# ZG-Mxx_MINI-v1_0.net
KiCad netlist of a schematic drawn in Altium Designer
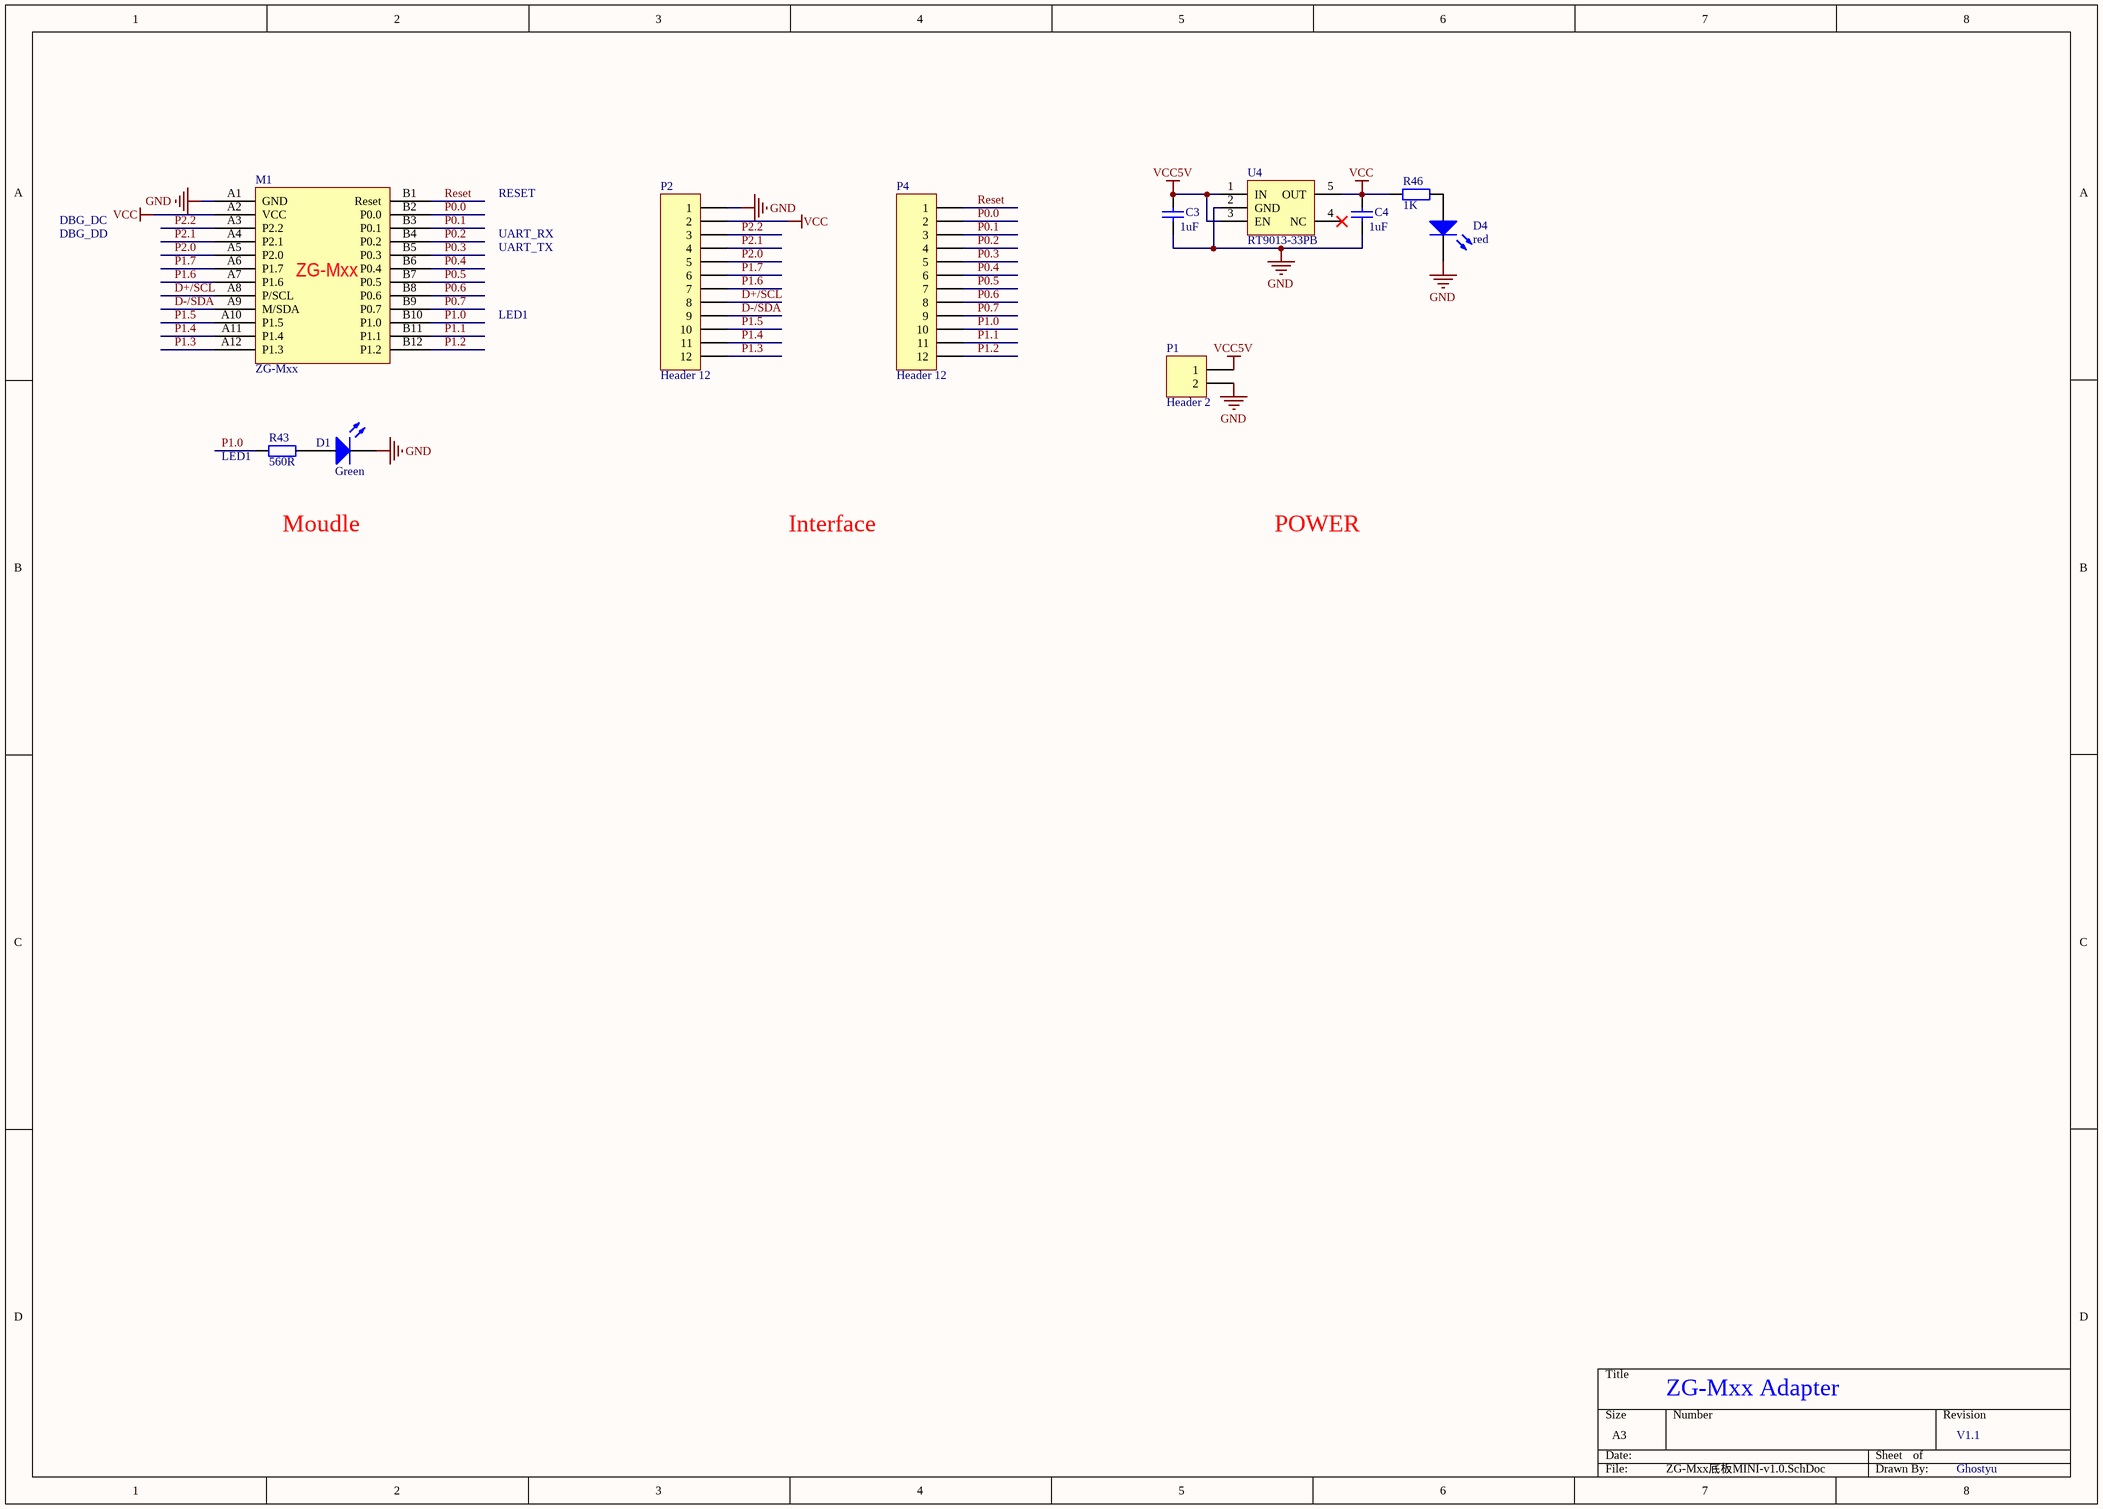
[diagram p0: ZG-Mxx底板MINI-v1.0.SchDoc]

(export (version "E")
  (design (tool "Eeschema 10.0.6"))
  (components
    (comp (ref "C3")
      (value "1uF")
      (footprint "R0603-S")
      (description "Capacitor")
      (fields (field (name "Comment") "Cap") (field (name "PUBLISHER") "Altium Limited"))
      (libsource (lib "Miscellaneous Devices") (part "Cap"))
    )
    (comp (ref "C4")
      (value "1uF")
      (footprint "R0603-S")
      (description "Capacitor")
      (fields (field (name "Comment") "Cap") (field (name "PUBLISHER") "Altium Limited"))
      (libsource (lib "Miscellaneous Devices") (part "Cap"))
    )
    (comp (ref "D1")
      (value "Green")
      (footprint "LED0805")
      (description "Typical RED, GREEN, YELLOW, AMBER GaAs LED")
      (fields (field (name "PUBLISHER") "Altium Limited"))
      (libsource (lib "Miscellaneous Devices") (part "LED2"))
    )
    (comp (ref "D4")
      (value "red")
      (footprint "LED0805")
      (description "Typical RED, GREEN, YELLOW, AMBER GaAs LED")
      (fields (field (name "PUBLISHER") "Altium Limited"))
      (libsource (lib "Miscellaneous Devices") (part "LED2"))
    )
    (comp (ref "M1") (value "ZG-Mxx") (footprint "ZG-M1/1E") (libsource (lib "ZG-Mxx") (part "ZG-Mxx")))
    (comp (ref "P1")
      (value "Header 2")
      (footprint "HDR1X2")
      (description "Header, 2-Pin")
      (fields (field (name "PUBLISHER") "Altium Limited"))
      (libsource (lib "Miscellaneous Connectors") (part "Header 2"))
    )
    (comp (ref "P2")
      (value "Header 12")
      (footprint "HDR2X6")
      (description "Header, 12-Pin")
      (fields (field (name "PUBLISHER") "Altium Limited"))
      (libsource (lib "Miscellaneous Connectors") (part "Header 12"))
    )
    (comp (ref "P4")
      (value "Header 12")
      (footprint "HDR2X6")
      (description "Header, 12-Pin")
      (fields (field (name "PUBLISHER") "Altium Limited"))
      (libsource (lib "Miscellaneous Connectors") (part "Header 12"))
    )
    (comp (ref "R43")
      (value "560R")
      (footprint "R0603-S")
      (description "Resistor")
      (fields (field (name "Comment") "Res2") (field (name "PUBLISHER") "Altium Limited"))
      (libsource (lib "Miscellaneous Devices") (part "Res2"))
    )
    (comp (ref "R46")
      (value "1K")
      (footprint "R0603-S")
      (description "Resistor")
      (fields (field (name "Comment") "Res2") (field (name "PUBLISHER") "Altium Limited"))
      (libsource (lib "Miscellaneous Devices") (part "Res2"))
    )
    (comp (ref "U4")
      (value "RT9013-33PB")
      (footprint "SOT23-5")
      (libsource (lib "Schlib") (part "RT9013-33PB"))
    )
  )
  (nets
    (net (code "1") (name "/D+{slash}SCL") (class "Default")
      (node (ref "M1") (pin "A8") (pinfunction "P/SCL_A8") (pintype "passive"))
      (node (ref "P2") (pin "8") (pinfunction "8_8") (pintype "passive"))
    )
    (net (code "2") (name "/D-{slash}SDA") (class "Default")
      (node (ref "M1") (pin "A9") (pinfunction "M/SDA_A9") (pintype "passive"))
      (node (ref "P2") (pin "9") (pinfunction "9_9") (pintype "passive"))
    )
    (net (code "3") (name "/P0.0") (class "Default")
      (node (ref "M1") (pin "B2") (pinfunction "P0.0_B2") (pintype "passive"))
      (node (ref "P4") (pin "2") (pinfunction "2_2") (pintype "passive"))
    )
    (net (code "4") (name "/P0.1") (class "Default")
      (node (ref "M1") (pin "B3") (pinfunction "P0.1_B3") (pintype "passive"))
      (node (ref "P4") (pin "3") (pinfunction "3_3") (pintype "passive"))
    )
    (net (code "5") (name "/P0.2") (class "Default")
      (node (ref "M1") (pin "B4") (pinfunction "P0.2_B4") (pintype "passive"))
      (node (ref "P4") (pin "4") (pinfunction "4_4") (pintype "passive"))
    )
    (net (code "6") (name "/P0.3") (class "Default")
      (node (ref "M1") (pin "B5") (pinfunction "P0.3_B5") (pintype "passive"))
      (node (ref "P4") (pin "5") (pinfunction "5_5") (pintype "passive"))
    )
    (net (code "7") (name "/P0.4") (class "Default")
      (node (ref "M1") (pin "B6") (pinfunction "P0.4_B6") (pintype "passive"))
      (node (ref "P4") (pin "6") (pinfunction "6_6") (pintype "passive"))
    )
    (net (code "8") (name "/P0.5") (class "Default")
      (node (ref "M1") (pin "B7") (pinfunction "P0.5_B7") (pintype "passive"))
      (node (ref "P4") (pin "7") (pinfunction "7_7") (pintype "passive"))
    )
    (net (code "9") (name "/P0.6") (class "Default")
      (node (ref "M1") (pin "B8") (pinfunction "P0.6_B8") (pintype "passive"))
      (node (ref "P4") (pin "8") (pinfunction "8_8") (pintype "passive"))
    )
    (net (code "10") (name "/P0.7") (class "Default")
      (node (ref "M1") (pin "B9") (pinfunction "P0.7_B9") (pintype "passive"))
      (node (ref "P4") (pin "9") (pinfunction "9_9") (pintype "passive"))
    )
    (net (code "11") (name "/P1.0") (class "Default")
      (node (ref "M1") (pin "B10") (pinfunction "P1.0_B10") (pintype "passive"))
      (node (ref "P4") (pin "10") (pinfunction "10_10") (pintype "passive"))
      (node (ref "R43") (pin "2") (pinfunction "2_2") (pintype "passive"))
    )
    (net (code "12") (name "/P1.1") (class "Default")
      (node (ref "M1") (pin "B11") (pinfunction "P1.1_B11") (pintype "passive"))
      (node (ref "P4") (pin "11") (pinfunction "11_11") (pintype "passive"))
    )
    (net (code "13") (name "/P1.2") (class "Default")
      (node (ref "M1") (pin "B12") (pinfunction "P1.2_B12") (pintype "passive"))
      (node (ref "P4") (pin "12") (pinfunction "12_12") (pintype "passive"))
    )
    (net (code "14") (name "/P1.3") (class "Default")
      (node (ref "M1") (pin "A12") (pinfunction "P1.3_A12") (pintype "passive"))
      (node (ref "P2") (pin "12") (pinfunction "12_12") (pintype "passive"))
    )
    (net (code "15") (name "/P1.4") (class "Default")
      (node (ref "M1") (pin "A11") (pinfunction "P1.4_A11") (pintype "passive"))
      (node (ref "P2") (pin "11") (pinfunction "11_11") (pintype "passive"))
    )
    (net (code "16") (name "/P1.5") (class "Default")
      (node (ref "M1") (pin "A10") (pinfunction "P1.5_A10") (pintype "passive"))
      (node (ref "P2") (pin "10") (pinfunction "10_10") (pintype "passive"))
    )
    (net (code "17") (name "/P1.6") (class "Default")
      (node (ref "M1") (pin "A7") (pinfunction "P1.6_A7") (pintype "passive"))
      (node (ref "P2") (pin "7") (pinfunction "7_7") (pintype "passive"))
    )
    (net (code "18") (name "/P1.7") (class "Default")
      (node (ref "M1") (pin "A6") (pinfunction "P1.7_A6") (pintype "passive"))
      (node (ref "P2") (pin "6") (pinfunction "6_6") (pintype "passive"))
    )
    (net (code "19") (name "/P2.0") (class "Default")
      (node (ref "M1") (pin "A5") (pinfunction "P2.0_A5") (pintype "passive"))
      (node (ref "P2") (pin "5") (pinfunction "5_5") (pintype "passive"))
    )
    (net (code "20") (name "/P2.1") (class "Default")
      (node (ref "M1") (pin "A4") (pinfunction "P2.1_A4") (pintype "passive"))
      (node (ref "P2") (pin "4") (pinfunction "4_4") (pintype "passive"))
    )
    (net (code "21") (name "/P2.2") (class "Default")
      (node (ref "M1") (pin "A3") (pinfunction "P2.2_A3") (pintype "passive"))
      (node (ref "P2") (pin "3") (pinfunction "3_3") (pintype "passive"))
    )
    (net (code "22") (name "/Reset") (class "Default")
      (node (ref "M1") (pin "B1") (pinfunction "Reset_B1") (pintype "passive"))
      (node (ref "P4") (pin "1") (pinfunction "1_1") (pintype "passive"))
    )
    (net (code "23") (name "GND") (class "Default")
      (node (ref "C3") (pin "2") (pinfunction "2_2") (pintype "passive"))
      (node (ref "C4") (pin "2") (pinfunction "2_2") (pintype "passive"))
      (node (ref "D1") (pin "2") (pinfunction "K_2") (pintype "passive"))
      (node (ref "D4") (pin "2") (pinfunction "K_2") (pintype "passive"))
      (node (ref "M1") (pin "A1") (pinfunction "GND_A1") (pintype "passive"))
      (node (ref "P1") (pin "2") (pinfunction "2_2") (pintype "passive"))
      (node (ref "P2") (pin "1") (pinfunction "1_1") (pintype "passive"))
      (node (ref "U4") (pin "2") (pinfunction "GND_2") (pintype "passive"))
    )
    (net (code "24") (name "Net-(D1-A)") (class "Default")
      (node (ref "D1") (pin "1") (pinfunction "A_1") (pintype "passive"))
      (node (ref "R43") (pin "1") (pinfunction "1_1") (pintype "passive"))
    )
    (net (code "25") (name "Net-(D4-A)") (class "Default")
      (node (ref "D4") (pin "1") (pinfunction "A_1") (pintype "passive"))
      (node (ref "R46") (pin "1") (pinfunction "1_1") (pintype "passive"))
    )
    (net (code "26") (name "VCC") (class "Default")
      (node (ref "C4") (pin "1") (pinfunction "1_1") (pintype "passive"))
      (node (ref "M1") (pin "A2") (pinfunction "VCC_A2") (pintype "passive"))
      (node (ref "P2") (pin "2") (pinfunction "2_2") (pintype "passive"))
      (node (ref "R46") (pin "2") (pinfunction "2_2") (pintype "passive"))
      (node (ref "U4") (pin "5") (pinfunction "OUT_5") (pintype "passive"))
    )
    (net (code "27") (name "VCC5V") (class "Default")
      (node (ref "C3") (pin "1") (pinfunction "1_1") (pintype "passive"))
      (node (ref "P1") (pin "1") (pinfunction "1_1") (pintype "passive"))
      (node (ref "U4") (pin "1") (pinfunction "IN_1") (pintype "passive"))
      (node (ref "U4") (pin "3") (pinfunction "EN_3") (pintype "passive"))
    )
    (net (code "28") (name "unconnected-(U4-NC-Pad4)") (class "Default")
      (node (ref "U4") (pin "4") (pinfunction "NC_4") (pintype "passive+no_connect"))
    )
  )
)
